# v_laszt.net
KiCad netlist of a schematic drawn in EAGLE
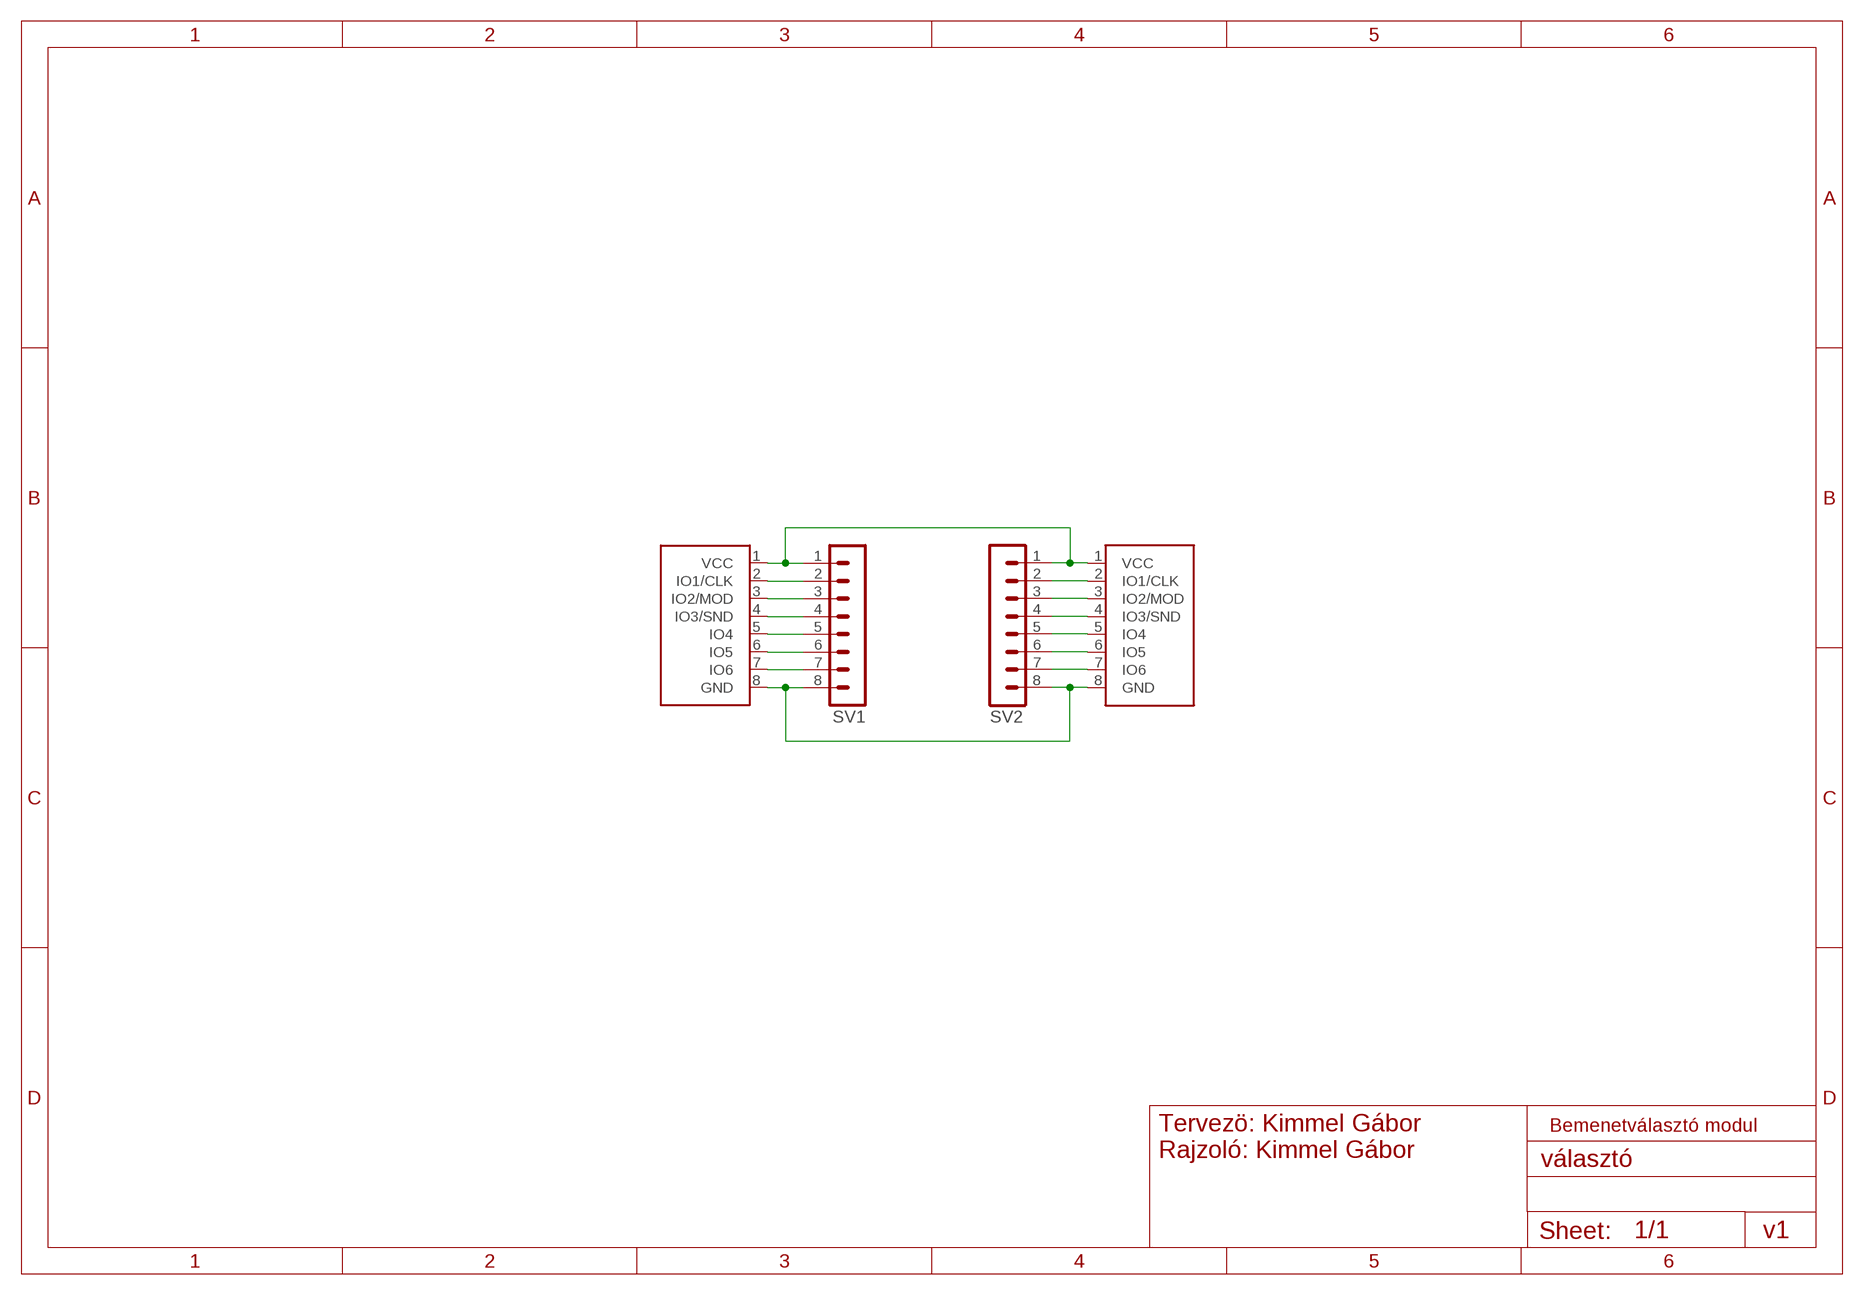
[diagram p0: schematic, sheet 1]

(export (version "E")
  (design (tool "Eeschema 10.0.6"))
  (components
    (comp (ref "SV1")
      (value "MA08-1")
      (footprint "eagle-import:MA08-1")
      (libsource (lib "eagle-import") (part "MA08-1"))
    )
    (comp (ref "SV2")
      (value "MA08-1")
      (footprint "eagle-import:MA08-1")
      (libsource (lib "eagle-import") (part "MA08-1"))
    )
    (comp (ref "U$1")
      (value "GANZ-CONNECTOR")
      (footprint "eagle-import:FE08W")
      (libsource (lib "eagle-import") (part "GANZ-CONNECTOR"))
    )
    (comp (ref "U$2")
      (value "GANZ-CONNECTOR-OUT")
      (footprint "eagle-import:MA08-1W")
      (libsource (lib "eagle-import") (part "GANZ-CONNECTOR-OUT"))
    )
  )
  (nets
    (net (code "1") (name "Net-(U$1-GND)") (class "Default")
      (node (ref "SV1") (pin "8") (pinfunction "8_8") (pintype "passive"))
      (node (ref "SV2") (pin "8") (pinfunction "8_8") (pintype "passive"))
      (node (ref "U$1") (pin "8") (pinfunction "GND_8") (pintype "bidirectional"))
      (node (ref "U$2") (pin "8") (pinfunction "GND_8") (pintype "bidirectional"))
    )
    (net (code "2") (name "Net-(U$1-IO1{slash}CLK)") (class "Default")
      (node (ref "SV1") (pin "2") (pinfunction "2_2") (pintype "passive"))
      (node (ref "U$1") (pin "2") (pinfunction "IO1/CLK_2") (pintype "bidirectional"))
    )
    (net (code "3") (name "Net-(U$1-IO2{slash}MOD)") (class "Default")
      (node (ref "SV1") (pin "3") (pinfunction "3_3") (pintype "passive"))
      (node (ref "U$1") (pin "3") (pinfunction "IO2/MOD_3") (pintype "bidirectional"))
    )
    (net (code "4") (name "Net-(U$1-IO3{slash}SND)") (class "Default")
      (node (ref "SV1") (pin "4") (pinfunction "4_4") (pintype "passive"))
      (node (ref "U$1") (pin "4") (pinfunction "IO3/SND_4") (pintype "bidirectional"))
    )
    (net (code "5") (name "Net-(U$1-IO4)") (class "Default")
      (node (ref "SV1") (pin "5") (pinfunction "5_5") (pintype "passive"))
      (node (ref "U$1") (pin "5") (pinfunction "IO4_5") (pintype "bidirectional"))
    )
    (net (code "6") (name "Net-(U$1-IO5)") (class "Default")
      (node (ref "SV1") (pin "6") (pinfunction "6_6") (pintype "passive"))
      (node (ref "U$1") (pin "6") (pinfunction "IO5_6") (pintype "bidirectional"))
    )
    (net (code "7") (name "Net-(U$1-IO6)") (class "Default")
      (node (ref "SV1") (pin "7") (pinfunction "7_7") (pintype "passive"))
      (node (ref "U$1") (pin "7") (pinfunction "IO6_7") (pintype "bidirectional"))
    )
    (net (code "8") (name "Net-(U$1-VCC)") (class "Default")
      (node (ref "SV1") (pin "1") (pinfunction "1_1") (pintype "passive"))
      (node (ref "SV2") (pin "1") (pinfunction "1_1") (pintype "passive"))
      (node (ref "U$1") (pin "1") (pinfunction "VCC_1") (pintype "bidirectional"))
      (node (ref "U$2") (pin "1") (pinfunction "VCC_1") (pintype "bidirectional"))
    )
    (net (code "9") (name "Net-(U$2-IO1{slash}CLK)") (class "Default")
      (node (ref "SV2") (pin "2") (pinfunction "2_2") (pintype "passive"))
      (node (ref "U$2") (pin "2") (pinfunction "IO1/CLK_2") (pintype "bidirectional"))
    )
    (net (code "10") (name "Net-(U$2-IO2{slash}MOD)") (class "Default")
      (node (ref "SV2") (pin "3") (pinfunction "3_3") (pintype "passive"))
      (node (ref "U$2") (pin "3") (pinfunction "IO2/MOD_3") (pintype "bidirectional"))
    )
    (net (code "11") (name "Net-(U$2-IO3{slash}SND)") (class "Default")
      (node (ref "SV2") (pin "4") (pinfunction "4_4") (pintype "passive"))
      (node (ref "U$2") (pin "4") (pinfunction "IO3/SND_4") (pintype "bidirectional"))
    )
    (net (code "12") (name "Net-(U$2-IO4)") (class "Default")
      (node (ref "SV2") (pin "5") (pinfunction "5_5") (pintype "passive"))
      (node (ref "U$2") (pin "5") (pinfunction "IO4_5") (pintype "bidirectional"))
    )
    (net (code "13") (name "Net-(U$2-IO5)") (class "Default")
      (node (ref "SV2") (pin "6") (pinfunction "6_6") (pintype "passive"))
      (node (ref "U$2") (pin "6") (pinfunction "IO5_6") (pintype "bidirectional"))
    )
    (net (code "14") (name "Net-(U$2-IO6)") (class "Default")
      (node (ref "SV2") (pin "7") (pinfunction "7_7") (pintype "passive"))
      (node (ref "U$2") (pin "7") (pinfunction "IO6_7") (pintype "bidirectional"))
    )
  )
)
